# power-optical.net
KiCad netlist of a schematic drawn in Altium Designer
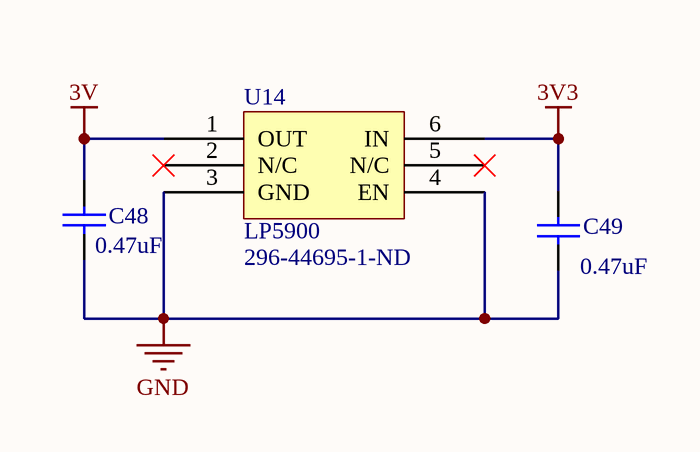
[diagram p0: power-optical.SchDoc]

(export (version "E")
  (design (tool "Eeschema 10.0.6"))
  (components
    (comp (ref "C48")
      (value "0.47uF")
      (footprint "C1206")
      (description "Capacitor (Semiconductor SIM Model)")
      (fields (field (name "Comment") "Cap Semi") (field (name "PUBLISHER") "Altium Limited"))
      (libsource (lib "Miscellaneous Devices") (part "Cap Semi"))
    )
    (comp (ref "C49")
      (value "0.47uF")
      (footprint "C1206")
      (description "Capacitor (Semiconductor SIM Model)")
      (fields (field (name "Comment") "Cap Semi") (field (name "PUBLISHER") "Altium Limited"))
      (libsource (lib "Miscellaneous Devices") (part "Cap Semi"))
    )
    (comp (ref "U14")
      (value "LP5900")
      (description "Low noise 3V low dropout regulator for analog and RF applications.")
      (fields (field (name "SUPPLIER PART NUMBER 1") "296-44695-1-ND"))
      (libsource (lib "PAY") (part "LP5900"))
    )
  )
  (nets
    (net (code "1") (name "3V") (class "Default")
      (node (ref "C48") (pin "2") (pinfunction "2_2") (pintype "passive"))
      (node (ref "U14") (pin "1") (pinfunction "OUT_1") (pintype "passive"))
    )
    (net (code "2") (name "3V3") (class "Default")
      (node (ref "C49") (pin "2") (pinfunction "2_2") (pintype "passive"))
      (node (ref "U14") (pin "6") (pinfunction "IN_6") (pintype "passive"))
    )
    (net (code "3") (name "GND") (class "Default")
      (node (ref "C48") (pin "1") (pinfunction "1_1") (pintype "passive"))
      (node (ref "C49") (pin "1") (pinfunction "1_1") (pintype "passive"))
      (node (ref "U14") (pin "3") (pinfunction "GND_3") (pintype "passive"))
      (node (ref "U14") (pin "4") (pinfunction "EN_4") (pintype "passive"))
    )
    (net (code "4") (name "unconnected-(U14-N{slash}C-Pad2)") (class "Default")
      (node (ref "U14") (pin "2") (pinfunction "N/C_2") (pintype "passive+no_connect"))
    )
    (net (code "5") (name "unconnected-(U14-N{slash}C-Pad5)") (class "Default")
      (node (ref "U14") (pin "5") (pinfunction "N/C_5") (pintype "passive+no_connect"))
    )
  )
)
